# relay.net
KiCad netlist of a schematic drawn in EAGLE
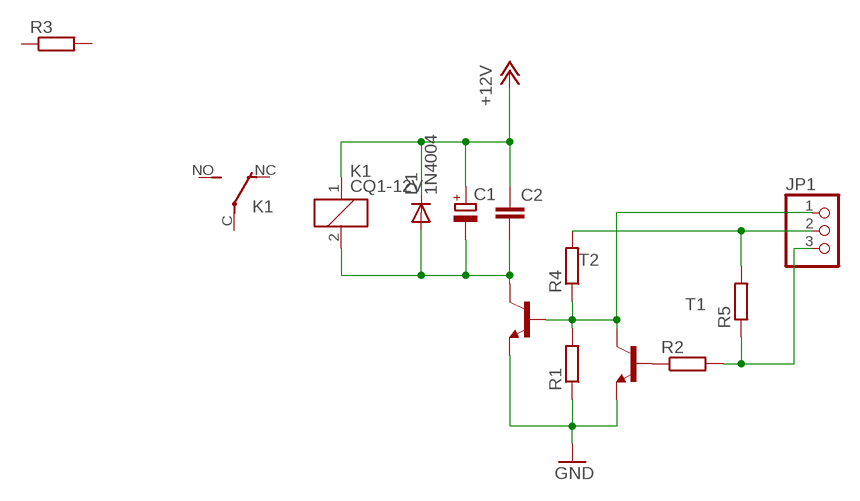
[diagram p0: schematic, sheet 1]

(export (version "E")
  (design (tool "Eeschema 10.0.6"))
  (components
    (comp (ref "C1")
      (value "CPOL-EUE5-13")
      (footprint "eagle-import:E5-13")
      (libsource (lib "eagle-import") (part "CPOL-EUE5-13"))
    )
    (comp (ref "C2")
      (value "C-EU050-025X075")
      (footprint "eagle-import:C050-025X075")
      (libsource (lib "eagle-import") (part "C-EU050-025X075"))
    )
    (comp (ref "D1")
      (value "1N4004")
      (footprint "eagle-import:DO41-10")
      (libsource (lib "eagle-import") (part "1N4004"))
    )
    (comp (ref "JP1")
      (value "PINHD-1X3")
      (footprint "eagle-import:1X03")
      (libsource (lib "eagle-import") (part "PINHD-1X3"))
    )
    (comp (ref "K1")
      (value "CQ1-12V")
      (footprint "eagle-import:CQ1")
      (libsource (lib "eagle-import") (part "CQ1-12V"))
    )
    (comp (ref "R1")
      (value "R-EU_0207/10")
      (footprint "eagle-import:0207_10")
      (libsource (lib "eagle-import") (part "R-EU_0207/10"))
    )
    (comp (ref "R2")
      (value "R-EU_0207/10")
      (footprint "eagle-import:0207_10")
      (libsource (lib "eagle-import") (part "R-EU_0207/10"))
    )
    (comp (ref "R3")
      (value "R-EU_0207/10")
      (footprint "eagle-import:0207_10")
      (libsource (lib "eagle-import") (part "R-EU_0207/10"))
    )
    (comp (ref "R4")
      (value "R-EU_0207/10")
      (footprint "eagle-import:0207_10")
      (libsource (lib "eagle-import") (part "R-EU_0207/10"))
    )
    (comp (ref "R5")
      (value "R-EU_0207/10")
      (footprint "eagle-import:0207_10")
      (libsource (lib "eagle-import") (part "R-EU_0207/10"))
    )
    (comp (ref "T1")
      (value "-NPN-TO92")
      (footprint "eagle-import:TO92")
      (libsource (lib "eagle-import") (part "-NPN-TO92"))
    )
    (comp (ref "T2")
      (value "-NPN-TO92")
      (footprint "eagle-import:TO92")
      (libsource (lib "eagle-import") (part "-NPN-TO92"))
    )
  )
  (nets
    (net (code "1") (name "+12V") (class "Default")
      (node (ref "C1") (pin "+") (pinfunction "+_+") (pintype "passive"))
      (node (ref "C2") (pin "1") (pinfunction "1_1") (pintype "passive"))
      (node (ref "D1") (pin "C") (pinfunction "C_C") (pintype "passive"))
      (node (ref "K1") (pin "1") (pinfunction "1_1") (pintype "passive"))
    )
    (net (code "2") (name "GND") (class "Default")
      (node (ref "R1") (pin "1") (pinfunction "1_1") (pintype "passive"))
      (node (ref "T1") (pin "1") (pinfunction "E_1") (pintype "passive"))
      (node (ref "T2") (pin "1") (pinfunction "E_1") (pintype "passive"))
    )
    (net (code "3") (name "Net-(JP1-Pad2)") (class "Default")
      (node (ref "JP1") (pin "2") (pinfunction "2_2") (pintype "passive"))
      (node (ref "R4") (pin "2") (pinfunction "2_2") (pintype "passive"))
      (node (ref "R5") (pin "2") (pinfunction "2_2") (pintype "passive"))
    )
    (net (code "4") (name "Net-(JP1-Pad3)") (class "Default")
      (node (ref "JP1") (pin "3") (pinfunction "3_3") (pintype "passive"))
      (node (ref "R2") (pin "2") (pinfunction "2_2") (pintype "passive"))
      (node (ref "R5") (pin "1") (pinfunction "1_1") (pintype "passive"))
    )
    (net (code "5") (name "Net-(T1-B)") (class "Default")
      (node (ref "R2") (pin "1") (pinfunction "1_1") (pintype "passive"))
      (node (ref "T1") (pin "2") (pinfunction "B_2") (pintype "passive"))
    )
    (net (code "6") (name "Net-(T1-C)") (class "Default")
      (node (ref "JP1") (pin "1") (pinfunction "1_1") (pintype "passive"))
      (node (ref "R1") (pin "2") (pinfunction "2_2") (pintype "passive"))
      (node (ref "R4") (pin "1") (pinfunction "1_1") (pintype "passive"))
      (node (ref "T1") (pin "3") (pinfunction "C_3") (pintype "passive"))
      (node (ref "T2") (pin "2") (pinfunction "B_2") (pintype "passive"))
    )
    (net (code "7") (name "Net-(T2-C)") (class "Default")
      (node (ref "C1") (pin "-") (pinfunction "-_-") (pintype "passive"))
      (node (ref "C2") (pin "2") (pinfunction "2_2") (pintype "passive"))
      (node (ref "D1") (pin "A") (pinfunction "A_A") (pintype "passive"))
      (node (ref "K1") (pin "2") (pinfunction "2_2") (pintype "passive"))
      (node (ref "T2") (pin "3") (pinfunction "C_3") (pintype "passive"))
    )
    (net (code "8") (name "unconnected-(K1B-O-PadNC)") (class "Default")
      (node (ref "K1") (pin "NC") (pinfunction "O_NC") (pintype "passive"))
    )
    (net (code "9") (name "unconnected-(K1B-P-PadC)") (class "Default")
      (node (ref "K1") (pin "C") (pinfunction "P_C") (pintype "passive"))
    )
    (net (code "10") (name "unconnected-(K1B-S-PadNO)") (class "Default")
      (node (ref "K1") (pin "NO") (pinfunction "S_NO") (pintype "passive"))
    )
    (net (code "11") (name "unconnected-(R3-Pad1)") (class "Default")
      (node (ref "R3") (pin "1") (pinfunction "1_1") (pintype "passive"))
    )
    (net (code "12") (name "unconnected-(R3-Pad2)") (class "Default")
      (node (ref "R3") (pin "2") (pinfunction "2_2") (pintype "passive"))
    )
  )
)
